# untitled.net
KiCad netlist of a schematic drawn in EAGLE
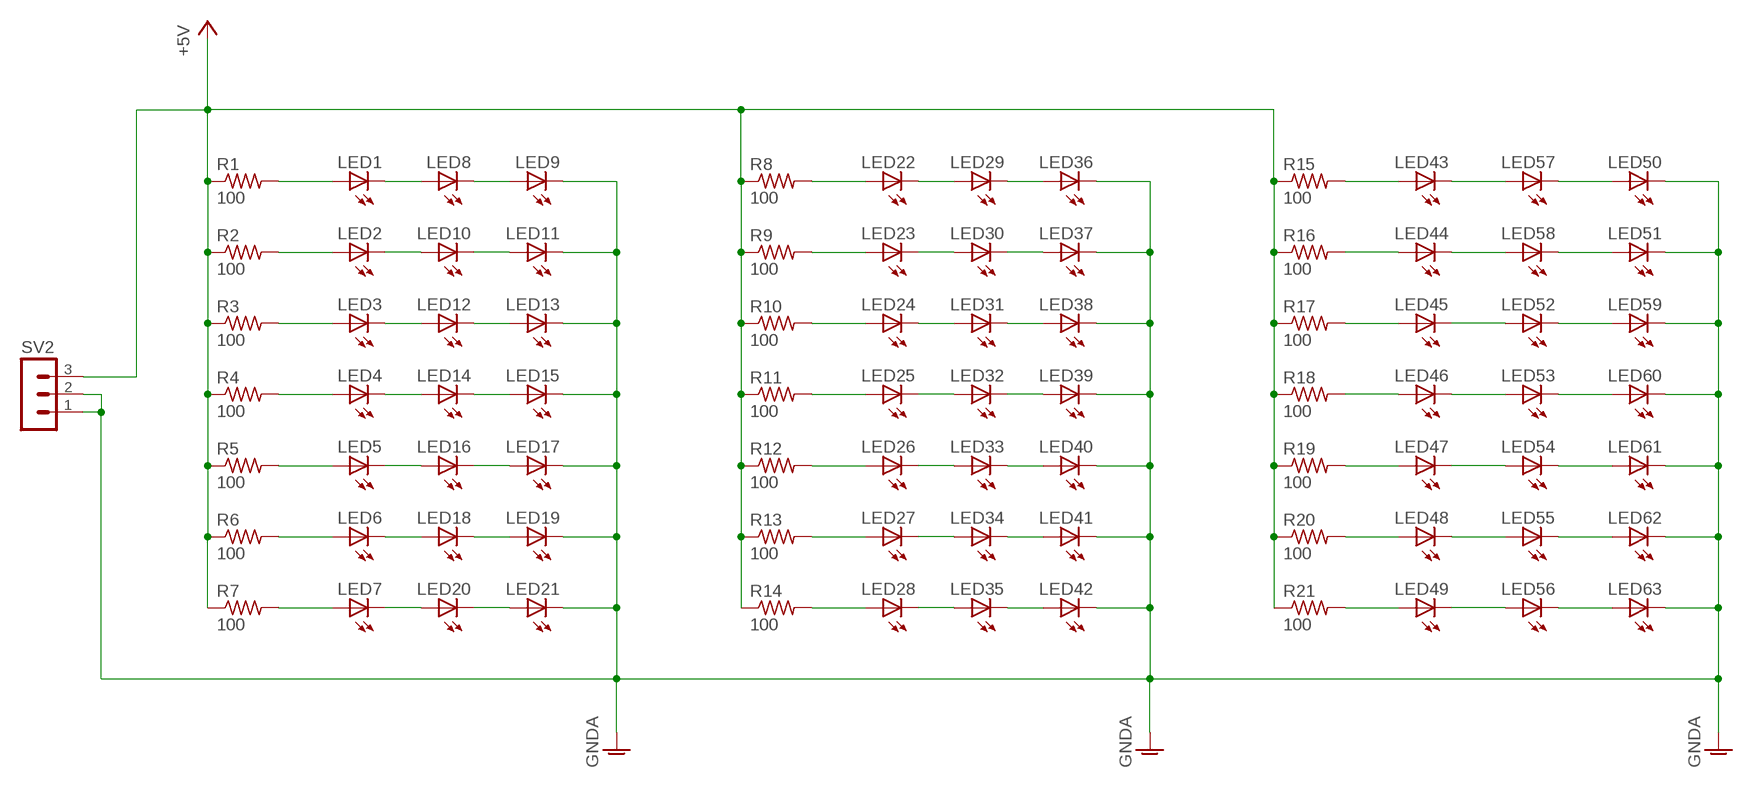
[diagram p0: schematic, sheet 1]

(export (version "E")
  (design (tool "Eeschema 10.0.6"))
  (components
    (comp (ref "LED1")
      (value "LED5MM")
      (footprint "eagle-import:LED5MM")
      (libsource (lib "eagle-import") (part "LED5MM"))
    )
    (comp (ref "LED2")
      (value "LED5MM")
      (footprint "eagle-import:LED5MM")
      (libsource (lib "eagle-import") (part "LED5MM"))
    )
    (comp (ref "LED3")
      (value "LED5MM")
      (footprint "eagle-import:LED5MM")
      (libsource (lib "eagle-import") (part "LED5MM"))
    )
    (comp (ref "LED4")
      (value "LED5MM")
      (footprint "eagle-import:LED5MM")
      (libsource (lib "eagle-import") (part "LED5MM"))
    )
    (comp (ref "LED5")
      (value "LED5MM")
      (footprint "eagle-import:LED5MM")
      (libsource (lib "eagle-import") (part "LED5MM"))
    )
    (comp (ref "LED6")
      (value "LED5MM")
      (footprint "eagle-import:LED5MM")
      (libsource (lib "eagle-import") (part "LED5MM"))
    )
    (comp (ref "LED7")
      (value "LED5MM")
      (footprint "eagle-import:LED5MM")
      (libsource (lib "eagle-import") (part "LED5MM"))
    )
    (comp (ref "LED8")
      (value "LED5MM")
      (footprint "eagle-import:LED5MM")
      (libsource (lib "eagle-import") (part "LED5MM"))
    )
    (comp (ref "LED9")
      (value "LED5MM")
      (footprint "eagle-import:LED5MM")
      (libsource (lib "eagle-import") (part "LED5MM"))
    )
    (comp (ref "LED10")
      (value "LED5MM")
      (footprint "eagle-import:LED5MM")
      (libsource (lib "eagle-import") (part "LED5MM"))
    )
    (comp (ref "LED11")
      (value "LED5MM")
      (footprint "eagle-import:LED5MM")
      (libsource (lib "eagle-import") (part "LED5MM"))
    )
    (comp (ref "LED12")
      (value "LED5MM")
      (footprint "eagle-import:LED5MM")
      (libsource (lib "eagle-import") (part "LED5MM"))
    )
    (comp (ref "LED13")
      (value "LED5MM")
      (footprint "eagle-import:LED5MM")
      (libsource (lib "eagle-import") (part "LED5MM"))
    )
    (comp (ref "LED14")
      (value "LED5MM")
      (footprint "eagle-import:LED5MM")
      (libsource (lib "eagle-import") (part "LED5MM"))
    )
    (comp (ref "LED15")
      (value "LED5MM")
      (footprint "eagle-import:LED5MM")
      (libsource (lib "eagle-import") (part "LED5MM"))
    )
    (comp (ref "LED16")
      (value "LED5MM")
      (footprint "eagle-import:LED5MM")
      (libsource (lib "eagle-import") (part "LED5MM"))
    )
    (comp (ref "LED17")
      (value "LED5MM")
      (footprint "eagle-import:LED5MM")
      (libsource (lib "eagle-import") (part "LED5MM"))
    )
    (comp (ref "LED18")
      (value "LED5MM")
      (footprint "eagle-import:LED5MM")
      (libsource (lib "eagle-import") (part "LED5MM"))
    )
    (comp (ref "LED19")
      (value "LED5MM")
      (footprint "eagle-import:LED5MM")
      (libsource (lib "eagle-import") (part "LED5MM"))
    )
    (comp (ref "LED20")
      (value "LED5MM")
      (footprint "eagle-import:LED5MM")
      (libsource (lib "eagle-import") (part "LED5MM"))
    )
    (comp (ref "LED21")
      (value "LED5MM")
      (footprint "eagle-import:LED5MM")
      (libsource (lib "eagle-import") (part "LED5MM"))
    )
    (comp (ref "LED22")
      (value "LED5MM")
      (footprint "eagle-import:LED5MM")
      (libsource (lib "eagle-import") (part "LED5MM"))
    )
    (comp (ref "LED23")
      (value "LED5MM")
      (footprint "eagle-import:LED5MM")
      (libsource (lib "eagle-import") (part "LED5MM"))
    )
    (comp (ref "LED24")
      (value "LED5MM")
      (footprint "eagle-import:LED5MM")
      (libsource (lib "eagle-import") (part "LED5MM"))
    )
    (comp (ref "LED25")
      (value "LED5MM")
      (footprint "eagle-import:LED5MM")
      (libsource (lib "eagle-import") (part "LED5MM"))
    )
    (comp (ref "LED26")
      (value "LED5MM")
      (footprint "eagle-import:LED5MM")
      (libsource (lib "eagle-import") (part "LED5MM"))
    )
    (comp (ref "LED27")
      (value "LED5MM")
      (footprint "eagle-import:LED5MM")
      (libsource (lib "eagle-import") (part "LED5MM"))
    )
    (comp (ref "LED28")
      (value "LED5MM")
      (footprint "eagle-import:LED5MM")
      (libsource (lib "eagle-import") (part "LED5MM"))
    )
    (comp (ref "LED29")
      (value "LED5MM")
      (footprint "eagle-import:LED5MM")
      (libsource (lib "eagle-import") (part "LED5MM"))
    )
    (comp (ref "LED30")
      (value "LED5MM")
      (footprint "eagle-import:LED5MM")
      (libsource (lib "eagle-import") (part "LED5MM"))
    )
    (comp (ref "LED31")
      (value "LED5MM")
      (footprint "eagle-import:LED5MM")
      (libsource (lib "eagle-import") (part "LED5MM"))
    )
    (comp (ref "LED32")
      (value "LED5MM")
      (footprint "eagle-import:LED5MM")
      (libsource (lib "eagle-import") (part "LED5MM"))
    )
    (comp (ref "LED33")
      (value "LED5MM")
      (footprint "eagle-import:LED5MM")
      (libsource (lib "eagle-import") (part "LED5MM"))
    )
    (comp (ref "LED34")
      (value "LED5MM")
      (footprint "eagle-import:LED5MM")
      (libsource (lib "eagle-import") (part "LED5MM"))
    )
    (comp (ref "LED35")
      (value "LED5MM")
      (footprint "eagle-import:LED5MM")
      (libsource (lib "eagle-import") (part "LED5MM"))
    )
    (comp (ref "LED36")
      (value "LED5MM")
      (footprint "eagle-import:LED5MM")
      (libsource (lib "eagle-import") (part "LED5MM"))
    )
    (comp (ref "LED37")
      (value "LED5MM")
      (footprint "eagle-import:LED5MM")
      (libsource (lib "eagle-import") (part "LED5MM"))
    )
    (comp (ref "LED38")
      (value "LED5MM")
      (footprint "eagle-import:LED5MM")
      (libsource (lib "eagle-import") (part "LED5MM"))
    )
    (comp (ref "LED39")
      (value "LED5MM")
      (footprint "eagle-import:LED5MM")
      (libsource (lib "eagle-import") (part "LED5MM"))
    )
    (comp (ref "LED40")
      (value "LED5MM")
      (footprint "eagle-import:LED5MM")
      (libsource (lib "eagle-import") (part "LED5MM"))
    )
    (comp (ref "LED41")
      (value "LED5MM")
      (footprint "eagle-import:LED5MM")
      (libsource (lib "eagle-import") (part "LED5MM"))
    )
    (comp (ref "LED42")
      (value "LED5MM")
      (footprint "eagle-import:LED5MM")
      (libsource (lib "eagle-import") (part "LED5MM"))
    )
    (comp (ref "LED43")
      (value "LED5MM")
      (footprint "eagle-import:LED5MM")
      (libsource (lib "eagle-import") (part "LED5MM"))
    )
    (comp (ref "LED44")
      (value "LED5MM")
      (footprint "eagle-import:LED5MM")
      (libsource (lib "eagle-import") (part "LED5MM"))
    )
    (comp (ref "LED45")
      (value "LED5MM")
      (footprint "eagle-import:LED5MM")
      (libsource (lib "eagle-import") (part "LED5MM"))
    )
    (comp (ref "LED46")
      (value "LED5MM")
      (footprint "eagle-import:LED5MM")
      (libsource (lib "eagle-import") (part "LED5MM"))
    )
    (comp (ref "LED47")
      (value "LED5MM")
      (footprint "eagle-import:LED5MM")
      (libsource (lib "eagle-import") (part "LED5MM"))
    )
    (comp (ref "LED48")
      (value "LED5MM")
      (footprint "eagle-import:LED5MM")
      (libsource (lib "eagle-import") (part "LED5MM"))
    )
    (comp (ref "LED49")
      (value "LED5MM")
      (footprint "eagle-import:LED5MM")
      (libsource (lib "eagle-import") (part "LED5MM"))
    )
    (comp (ref "LED50")
      (value "LED5MM")
      (footprint "eagle-import:LED5MM")
      (libsource (lib "eagle-import") (part "LED5MM"))
    )
    (comp (ref "LED51")
      (value "LED5MM")
      (footprint "eagle-import:LED5MM")
      (libsource (lib "eagle-import") (part "LED5MM"))
    )
    (comp (ref "LED52")
      (value "LED5MM")
      (footprint "eagle-import:LED5MM")
      (libsource (lib "eagle-import") (part "LED5MM"))
    )
    (comp (ref "LED53")
      (value "LED5MM")
      (footprint "eagle-import:LED5MM")
      (libsource (lib "eagle-import") (part "LED5MM"))
    )
    (comp (ref "LED54")
      (value "LED5MM")
      (footprint "eagle-import:LED5MM")
      (libsource (lib "eagle-import") (part "LED5MM"))
    )
    (comp (ref "LED55")
      (value "LED5MM")
      (footprint "eagle-import:LED5MM")
      (libsource (lib "eagle-import") (part "LED5MM"))
    )
    (comp (ref "LED56")
      (value "LED5MM")
      (footprint "eagle-import:LED5MM")
      (libsource (lib "eagle-import") (part "LED5MM"))
    )
    (comp (ref "LED57")
      (value "LED5MM")
      (footprint "eagle-import:LED5MM")
      (libsource (lib "eagle-import") (part "LED5MM"))
    )
    (comp (ref "LED58")
      (value "LED5MM")
      (footprint "eagle-import:LED5MM")
      (libsource (lib "eagle-import") (part "LED5MM"))
    )
    (comp (ref "LED59")
      (value "LED5MM")
      (footprint "eagle-import:LED5MM")
      (libsource (lib "eagle-import") (part "LED5MM"))
    )
    (comp (ref "LED60")
      (value "LED5MM")
      (footprint "eagle-import:LED5MM")
      (libsource (lib "eagle-import") (part "LED5MM"))
    )
    (comp (ref "LED61")
      (value "LED5MM")
      (footprint "eagle-import:LED5MM")
      (libsource (lib "eagle-import") (part "LED5MM"))
    )
    (comp (ref "LED62")
      (value "LED5MM")
      (footprint "eagle-import:LED5MM")
      (libsource (lib "eagle-import") (part "LED5MM"))
    )
    (comp (ref "LED63")
      (value "LED5MM")
      (footprint "eagle-import:LED5MM")
      (libsource (lib "eagle-import") (part "LED5MM"))
    )
    (comp (ref "R1")
      (value "100")
      (footprint "eagle-import:0204_5")
      (libsource (lib "eagle-import") (part "R-US_0204/5"))
    )
    (comp (ref "R2")
      (value "100")
      (footprint "eagle-import:0204_5")
      (libsource (lib "eagle-import") (part "R-US_0204/5"))
    )
    (comp (ref "R3")
      (value "100")
      (footprint "eagle-import:0204_5")
      (libsource (lib "eagle-import") (part "R-US_0204/5"))
    )
    (comp (ref "R4")
      (value "100")
      (footprint "eagle-import:0204_5")
      (libsource (lib "eagle-import") (part "R-US_0204/5"))
    )
    (comp (ref "R5")
      (value "100")
      (footprint "eagle-import:0204_5")
      (libsource (lib "eagle-import") (part "R-US_0204/5"))
    )
    (comp (ref "R6")
      (value "100")
      (footprint "eagle-import:0204_5")
      (libsource (lib "eagle-import") (part "R-US_0204/5"))
    )
    (comp (ref "R7")
      (value "100")
      (footprint "eagle-import:0204_5")
      (libsource (lib "eagle-import") (part "R-US_0204/5"))
    )
    (comp (ref "R8")
      (value "100")
      (footprint "eagle-import:0204_5")
      (libsource (lib "eagle-import") (part "R-US_0204/5"))
    )
    (comp (ref "R9")
      (value "100")
      (footprint "eagle-import:0204_5")
      (libsource (lib "eagle-import") (part "R-US_0204/5"))
    )
    (comp (ref "R10")
      (value "100")
      (footprint "eagle-import:0204_5")
      (libsource (lib "eagle-import") (part "R-US_0204/5"))
    )
    (comp (ref "R11")
      (value "100")
      (footprint "eagle-import:0204_5")
      (libsource (lib "eagle-import") (part "R-US_0204/5"))
    )
    (comp (ref "R12")
      (value "100")
      (footprint "eagle-import:0204_5")
      (libsource (lib "eagle-import") (part "R-US_0204/5"))
    )
    (comp (ref "R13")
      (value "100")
      (footprint "eagle-import:0204_5")
      (libsource (lib "eagle-import") (part "R-US_0204/5"))
    )
    (comp (ref "R14")
      (value "100")
      (footprint "eagle-import:0204_5")
      (libsource (lib "eagle-import") (part "R-US_0204/5"))
    )
    (comp (ref "R15")
      (value "100")
      (footprint "eagle-import:0204_5")
      (libsource (lib "eagle-import") (part "R-US_0204/5"))
    )
    (comp (ref "R16")
      (value "100")
      (footprint "eagle-import:0204_5")
      (libsource (lib "eagle-import") (part "R-US_0204/5"))
    )
    (comp (ref "R17")
      (value "100")
      (footprint "eagle-import:0204_5")
      (libsource (lib "eagle-import") (part "R-US_0204/5"))
    )
    (comp (ref "R18")
      (value "100")
      (footprint "eagle-import:0204_5")
      (libsource (lib "eagle-import") (part "R-US_0204/5"))
    )
    (comp (ref "R19")
      (value "100")
      (footprint "eagle-import:0204_5")
      (libsource (lib "eagle-import") (part "R-US_0204/5"))
    )
    (comp (ref "R20")
      (value "100")
      (footprint "eagle-import:0204_5")
      (libsource (lib "eagle-import") (part "R-US_0204/5"))
    )
    (comp (ref "R21")
      (value "100")
      (footprint "eagle-import:0204_5")
      (libsource (lib "eagle-import") (part "R-US_0204/5"))
    )
    (comp (ref "SV2")
      (value "MA03-1")
      (footprint "eagle-import:MA03-1")
      (libsource (lib "eagle-import") (part "MA03-1"))
    )
  )
  (nets
    (net (code "1") (name "+5V") (class "Default")
      (node (ref "R1") (pin "1") (pinfunction "1_1") (pintype "passive"))
      (node (ref "R10") (pin "1") (pinfunction "1_1") (pintype "passive"))
      (node (ref "R11") (pin "1") (pinfunction "1_1") (pintype "passive"))
      (node (ref "R12") (pin "1") (pinfunction "1_1") (pintype "passive"))
      (node (ref "R13") (pin "1") (pinfunction "1_1") (pintype "passive"))
      (node (ref "R14") (pin "1") (pinfunction "1_1") (pintype "passive"))
      (node (ref "R15") (pin "1") (pinfunction "1_1") (pintype "passive"))
      (node (ref "R16") (pin "1") (pinfunction "1_1") (pintype "passive"))
      (node (ref "R17") (pin "1") (pinfunction "1_1") (pintype "passive"))
      (node (ref "R18") (pin "1") (pinfunction "1_1") (pintype "passive"))
      (node (ref "R19") (pin "1") (pinfunction "1_1") (pintype "passive"))
      (node (ref "R2") (pin "1") (pinfunction "1_1") (pintype "passive"))
      (node (ref "R20") (pin "1") (pinfunction "1_1") (pintype "passive"))
      (node (ref "R21") (pin "1") (pinfunction "1_1") (pintype "passive"))
      (node (ref "R3") (pin "1") (pinfunction "1_1") (pintype "passive"))
      (node (ref "R4") (pin "1") (pinfunction "1_1") (pintype "passive"))
      (node (ref "R5") (pin "1") (pinfunction "1_1") (pintype "passive"))
      (node (ref "R6") (pin "1") (pinfunction "1_1") (pintype "passive"))
      (node (ref "R7") (pin "1") (pinfunction "1_1") (pintype "passive"))
      (node (ref "R8") (pin "1") (pinfunction "1_1") (pintype "passive"))
      (node (ref "R9") (pin "1") (pinfunction "1_1") (pintype "passive"))
      (node (ref "SV2") (pin "3") (pinfunction "3_3") (pintype "passive"))
    )
    (net (code "2") (name "GNDA") (class "Default")
      (node (ref "LED11") (pin "K") (pinfunction "C_K") (pintype "passive"))
      (node (ref "LED13") (pin "K") (pinfunction "C_K") (pintype "passive"))
      (node (ref "LED15") (pin "K") (pinfunction "C_K") (pintype "passive"))
      (node (ref "LED17") (pin "K") (pinfunction "C_K") (pintype "passive"))
      (node (ref "LED19") (pin "K") (pinfunction "C_K") (pintype "passive"))
      (node (ref "LED21") (pin "K") (pinfunction "C_K") (pintype "passive"))
      (node (ref "LED36") (pin "K") (pinfunction "C_K") (pintype "passive"))
      (node (ref "LED37") (pin "K") (pinfunction "C_K") (pintype "passive"))
      (node (ref "LED38") (pin "K") (pinfunction "C_K") (pintype "passive"))
      (node (ref "LED39") (pin "K") (pinfunction "C_K") (pintype "passive"))
      (node (ref "LED40") (pin "K") (pinfunction "C_K") (pintype "passive"))
      (node (ref "LED41") (pin "K") (pinfunction "C_K") (pintype "passive"))
      (node (ref "LED42") (pin "K") (pinfunction "C_K") (pintype "passive"))
      (node (ref "LED50") (pin "K") (pinfunction "C_K") (pintype "passive"))
      (node (ref "LED51") (pin "K") (pinfunction "C_K") (pintype "passive"))
      (node (ref "LED59") (pin "K") (pinfunction "C_K") (pintype "passive"))
      (node (ref "LED60") (pin "K") (pinfunction "C_K") (pintype "passive"))
      (node (ref "LED61") (pin "K") (pinfunction "C_K") (pintype "passive"))
      (node (ref "LED62") (pin "K") (pinfunction "C_K") (pintype "passive"))
      (node (ref "LED63") (pin "K") (pinfunction "C_K") (pintype "passive"))
      (node (ref "LED9") (pin "K") (pinfunction "C_K") (pintype "passive"))
      (node (ref "SV2") (pin "1") (pinfunction "1_1") (pintype "passive"))
      (node (ref "SV2") (pin "2") (pinfunction "2_2") (pintype "passive"))
    )
    (net (code "3") (name "Net-(LED1-C)") (class "Default")
      (node (ref "LED1") (pin "K") (pinfunction "C_K") (pintype "passive"))
      (node (ref "LED8") (pin "A") (pinfunction "A_A") (pintype "passive"))
    )
    (net (code "4") (name "Net-(LED1-PadA)") (class "Default")
      (node (ref "LED1") (pin "A") (pinfunction "A_A") (pintype "passive"))
      (node (ref "R1") (pin "2") (pinfunction "2_2") (pintype "passive"))
    )
    (net (code "5") (name "Net-(LED2-C)") (class "Default")
      (node (ref "LED10") (pin "A") (pinfunction "A_A") (pintype "passive"))
      (node (ref "LED2") (pin "K") (pinfunction "C_K") (pintype "passive"))
    )
    (net (code "6") (name "Net-(LED2-PadA)") (class "Default")
      (node (ref "LED2") (pin "A") (pinfunction "A_A") (pintype "passive"))
      (node (ref "R2") (pin "2") (pinfunction "2_2") (pintype "passive"))
    )
    (net (code "7") (name "Net-(LED3-C)") (class "Default")
      (node (ref "LED12") (pin "A") (pinfunction "A_A") (pintype "passive"))
      (node (ref "LED3") (pin "K") (pinfunction "C_K") (pintype "passive"))
    )
    (net (code "8") (name "Net-(LED3-PadA)") (class "Default")
      (node (ref "LED3") (pin "A") (pinfunction "A_A") (pintype "passive"))
      (node (ref "R3") (pin "2") (pinfunction "2_2") (pintype "passive"))
    )
    (net (code "9") (name "Net-(LED4-C)") (class "Default")
      (node (ref "LED14") (pin "A") (pinfunction "A_A") (pintype "passive"))
      (node (ref "LED4") (pin "K") (pinfunction "C_K") (pintype "passive"))
    )
    (net (code "10") (name "Net-(LED4-PadA)") (class "Default")
      (node (ref "LED4") (pin "A") (pinfunction "A_A") (pintype "passive"))
      (node (ref "R4") (pin "2") (pinfunction "2_2") (pintype "passive"))
    )
    (net (code "11") (name "Net-(LED5-C)") (class "Default")
      (node (ref "LED16") (pin "A") (pinfunction "A_A") (pintype "passive"))
      (node (ref "LED5") (pin "K") (pinfunction "C_K") (pintype "passive"))
    )
    (net (code "12") (name "Net-(LED5-PadA)") (class "Default")
      (node (ref "LED5") (pin "A") (pinfunction "A_A") (pintype "passive"))
      (node (ref "R5") (pin "2") (pinfunction "2_2") (pintype "passive"))
    )
    (net (code "13") (name "Net-(LED6-C)") (class "Default")
      (node (ref "LED18") (pin "A") (pinfunction "A_A") (pintype "passive"))
      (node (ref "LED6") (pin "K") (pinfunction "C_K") (pintype "passive"))
    )
    (net (code "14") (name "Net-(LED6-PadA)") (class "Default")
      (node (ref "LED6") (pin "A") (pinfunction "A_A") (pintype "passive"))
      (node (ref "R6") (pin "2") (pinfunction "2_2") (pintype "passive"))
    )
    (net (code "15") (name "Net-(LED7-C)") (class "Default")
      (node (ref "LED20") (pin "A") (pinfunction "A_A") (pintype "passive"))
      (node (ref "LED7") (pin "K") (pinfunction "C_K") (pintype "passive"))
    )
    (net (code "16") (name "Net-(LED7-PadA)") (class "Default")
      (node (ref "LED7") (pin "A") (pinfunction "A_A") (pintype "passive"))
      (node (ref "R7") (pin "2") (pinfunction "2_2") (pintype "passive"))
    )
    (net (code "17") (name "Net-(LED8-C)") (class "Default")
      (node (ref "LED8") (pin "K") (pinfunction "C_K") (pintype "passive"))
      (node (ref "LED9") (pin "A") (pinfunction "A_A") (pintype "passive"))
    )
    (net (code "18") (name "Net-(LED10-C)") (class "Default")
      (node (ref "LED10") (pin "K") (pinfunction "C_K") (pintype "passive"))
      (node (ref "LED11") (pin "A") (pinfunction "A_A") (pintype "passive"))
    )
    (net (code "19") (name "Net-(LED12-C)") (class "Default")
      (node (ref "LED12") (pin "K") (pinfunction "C_K") (pintype "passive"))
      (node (ref "LED13") (pin "A") (pinfunction "A_A") (pintype "passive"))
    )
    (net (code "20") (name "Net-(LED14-C)") (class "Default")
      (node (ref "LED14") (pin "K") (pinfunction "C_K") (pintype "passive"))
      (node (ref "LED15") (pin "A") (pinfunction "A_A") (pintype "passive"))
    )
    (net (code "21") (name "Net-(LED16-C)") (class "Default")
      (node (ref "LED16") (pin "K") (pinfunction "C_K") (pintype "passive"))
      (node (ref "LED17") (pin "A") (pinfunction "A_A") (pintype "passive"))
    )
    (net (code "22") (name "Net-(LED18-C)") (class "Default")
      (node (ref "LED18") (pin "K") (pinfunction "C_K") (pintype "passive"))
      (node (ref "LED19") (pin "A") (pinfunction "A_A") (pintype "passive"))
    )
    (net (code "23") (name "Net-(LED20-C)") (class "Default")
      (node (ref "LED20") (pin "K") (pinfunction "C_K") (pintype "passive"))
      (node (ref "LED21") (pin "A") (pinfunction "A_A") (pintype "passive"))
    )
    (net (code "24") (name "Net-(LED22-C)") (class "Default")
      (node (ref "LED22") (pin "K") (pinfunction "C_K") (pintype "passive"))
      (node (ref "LED29") (pin "A") (pinfunction "A_A") (pintype "passive"))
    )
    (net (code "25") (name "Net-(LED22-PadA)") (class "Default")
      (node (ref "LED22") (pin "A") (pinfunction "A_A") (pintype "passive"))
      (node (ref "R8") (pin "2") (pinfunction "2_2") (pintype "passive"))
    )
    (net (code "26") (name "Net-(LED23-C)") (class "Default")
      (node (ref "LED23") (pin "K") (pinfunction "C_K") (pintype "passive"))
      (node (ref "LED30") (pin "A") (pinfunction "A_A") (pintype "passive"))
    )
    (net (code "27") (name "Net-(LED23-PadA)") (class "Default")
      (node (ref "LED23") (pin "A") (pinfunction "A_A") (pintype "passive"))
      (node (ref "R9") (pin "2") (pinfunction "2_2") (pintype "passive"))
    )
    (net (code "28") (name "Net-(LED24-C)") (class "Default")
      (node (ref "LED24") (pin "K") (pinfunction "C_K") (pintype "passive"))
      (node (ref "LED31") (pin "A") (pinfunction "A_A") (pintype "passive"))
    )
    (net (code "29") (name "Net-(LED24-PadA)") (class "Default")
      (node (ref "LED24") (pin "A") (pinfunction "A_A") (pintype "passive"))
      (node (ref "R10") (pin "2") (pinfunction "2_2") (pintype "passive"))
    )
    (net (code "30") (name "Net-(LED25-C)") (class "Default")
      (node (ref "LED25") (pin "K") (pinfunction "C_K") (pintype "passive"))
      (node (ref "LED32") (pin "A") (pinfunction "A_A") (pintype "passive"))
    )
    (net (code "31") (name "Net-(LED25-PadA)") (class "Default")
      (node (ref "LED25") (pin "A") (pinfunction "A_A") (pintype "passive"))
      (node (ref "R11") (pin "2") (pinfunction "2_2") (pintype "passive"))
    )
    (net (code "32") (name "Net-(LED26-C)") (class "Default")
      (node (ref "LED26") (pin "K") (pinfunction "C_K") (pintype "passive"))
      (node (ref "LED33") (pin "A") (pinfunction "A_A") (pintype "passive"))
    )
    (net (code "33") (name "Net-(LED26-PadA)") (class "Default")
      (node (ref "LED26") (pin "A") (pinfunction "A_A") (pintype "passive"))
      (node (ref "R12") (pin "2") (pinfunction "2_2") (pintype "passive"))
    )
    (net (code "34") (name "Net-(LED27-C)") (class "Default")
      (node (ref "LED27") (pin "K") (pinfunction "C_K") (pintype "passive"))
      (node (ref "LED34") (pin "A") (pinfunction "A_A") (pintype "passive"))
    )
    (net (code "35") (name "Net-(LED27-PadA)") (class "Default")
      (node (ref "LED27") (pin "A") (pinfunction "A_A") (pintype "passive"))
      (node (ref "R13") (pin "2") (pinfunction "2_2") (pintype "passive"))
    )
    (net (code "36") (name "Net-(LED28-C)") (class "Default")
      (node (ref "LED28") (pin "K") (pinfunction "C_K") (pintype "passive"))
      (node (ref "LED35") (pin "A") (pinfunction "A_A") (pintype "passive"))
    )
    (net (code "37") (name "Net-(LED28-PadA)") (class "Default")
      (node (ref "LED28") (pin "A") (pinfunction "A_A") (pintype "passive"))
      (node (ref "R14") (pin "2") (pinfunction "2_2") (pintype "passive"))
    )
    (net (code "38") (name "Net-(LED29-C)") (class "Default")
      (node (ref "LED29") (pin "K") (pinfunction "C_K") (pintype "passive"))
      (node (ref "LED36") (pin "A") (pinfunction "A_A") (pintype "passive"))
    )
    (net (code "39") (name "Net-(LED30-C)") (class "Default")
      (node (ref "LED30") (pin "K") (pinfunction "C_K") (pintype "passive"))
      (node (ref "LED37") (pin "A") (pinfunction "A_A") (pintype "passive"))
    )
    (net (code "40") (name "Net-(LED31-C)") (class "Default")
      (node (ref "LED31") (pin "K") (pinfunction "C_K") (pintype "passive"))
      (node (ref "LED38") (pin "A") (pinfunction "A_A") (pintype "passive"))
    )
    (net (code "41") (name "Net-(LED32-C)") (class "Default")
      (node (ref "LED32") (pin "K") (pinfunction "C_K") (pintype "passive"))
      (node (ref "LED39") (pin "A") (pinfunction "A_A") (pintype "passive"))
    )
    (net (code "42") (name "Net-(LED33-C)") (class "Default")
      (node (ref "LED33") (pin "K") (pinfunction "C_K") (pintype "passive"))
      (node (ref "LED40") (pin "A") (pinfunction "A_A") (pintype "passive"))
    )
    (net (code "43") (name "Net-(LED34-C)") (class "Default")
      (node (ref "LED34") (pin "K") (pinfunction "C_K") (pintype "passive"))
      (node (ref "LED41") (pin "A") (pinfunction "A_A") (pintype "passive"))
    )
    (net (code "44") (name "Net-(LED35-C)") (class "Default")
      (node (ref "LED35") (pin "K") (pinfunction "C_K") (pintype "passive"))
      (node (ref "LED42") (pin "A") (pinfunction "A_A") (pintype "passive"))
    )
    (net (code "45") (name "Net-(LED43-C)") (class "Default")
      (node (ref "LED43") (pin "K") (pinfunction "C_K") (pintype "passive"))
      (node (ref "LED57") (pin "A") (pinfunction "A_A") (pintype "passive"))
    )
    (net (code "46") (name "Net-(LED43-PadA)") (class "Default")
      (node (ref "LED43") (pin "A") (pinfunction "A_A") (pintype "passive"))
      (node (ref "R15") (pin "2") (pinfunction "2_2") (pintype "passive"))
    )
    (net (code "47") (name "Net-(LED44-C)") (class "Default")
      (node (ref "LED44") (pin "K") (pinfunction "C_K") (pintype "passive"))
      (node (ref "LED58") (pin "A") (pinfunction "A_A") (pintype "passive"))
    )
    (net (code "48") (name "Net-(LED44-PadA)") (class "Default")
      (node (ref "LED44") (pin "A") (pinfunction "A_A") (pintype "passive"))
      (node (ref "R16") (pin "2") (pinfunction "2_2") (pintype "passive"))
    )
    (net (code "49") (name "Net-(LED45-C)") (class "Default")
      (node (ref "LED45") (pin "K") (pinfunction "C_K") (pintype "passive"))
      (node (ref "LED52") (pin "A") (pinfunction "A_A") (pintype "passive"))
    )
    (net (code "50") (name "Net-(LED45-PadA)") (class "Default")
      (node (ref "LED45") (pin "A") (pinfunction "A_A") (pintype "passive"))
      (node (ref "R17") (pin "2") (pinfunction "2_2") (pintype "passive"))
    )
    (net (code "51") (name "Net-(LED46-C)") (class "Default")
      (node (ref "LED46") (pin "K") (pinfunction "C_K") (pintype "passive"))
      (node (ref "LED53") (pin "A") (pinfunction "A_A") (pintype "passive"))
    )
    (net (code "52") (name "Net-(LED46-PadA)") (class "Default")
      (node (ref "LED46") (pin "A") (pinfunction "A_A") (pintype "passive"))
      (node (ref "R18") (pin "2") (pinfunction "2_2") (pintype "passive"))
    )
    (net (code "53") (name "Net-(LED47-C)") (class "Default")
      (node (ref "LED47") (pin "K") (pinfunction "C_K") (pintype "passive"))
      (node (ref "LED54") (pin "A") (pinfunction "A_A") (pintype "passive"))
    )
    (net (code "54") (name "Net-(LED47-PadA)") (class "Default")
      (node (ref "LED47") (pin "A") (pinfunction "A_A") (pintype "passive"))
      (node (ref "R19") (pin "2") (pinfunction "2_2") (pintype "passive"))
    )
    (net (code "55") (name "Net-(LED48-C)") (class "Default")
      (node (ref "LED48") (pin "K") (pinfunction "C_K") (pintype "passive"))
      (node (ref "LED55") (pin "A") (pinfunction "A_A") (pintype "passive"))
    )
    (net (code "56") (name "Net-(LED48-PadA)") (class "Default")
      (node (ref "LED48") (pin "A") (pinfunction "A_A") (pintype "passive"))
      (node (ref "R20") (pin "2") (pinfunction "2_2") (pintype "passive"))
    )
    (net (code "57") (name "Net-(LED49-C)") (class "Default")
      (node (ref "LED49") (pin "K") (pinfunction "C_K") (pintype "passive"))
      (node (ref "LED56") (pin "A") (pinfunction "A_A") (pintype "passive"))
    )
    (net (code "58") (name "Net-(LED49-PadA)") (class "Default")
      (node (ref "LED49") (pin "A") (pinfunction "A_A") (pintype "passive"))
      (node (ref "R21") (pin "2") (pinfunction "2_2") (pintype "passive"))
    )
    (net (code "59") (name "Net-(LED52-C)") (class "Default")
      (node (ref "LED52") (pin "K") (pinfunction "C_K") (pintype "passive"))
      (node (ref "LED59") (pin "A") (pinfunction "A_A") (pintype "passive"))
    )
    (net (code "60") (name "Net-(LED53-C)") (class "Default")
      (node (ref "LED53") (pin "K") (pinfunction "C_K") (pintype "passive"))
      (node (ref "LED60") (pin "A") (pinfunction "A_A") (pintype "passive"))
    )
    (net (code "61") (name "Net-(LED54-C)") (class "Default")
      (node (ref "LED54") (pin "K") (pinfunction "C_K") (pintype "passive"))
      (node (ref "LED61") (pin "A") (pinfunction "A_A") (pintype "passive"))
    )
    (net (code "62") (name "Net-(LED55-C)") (class "Default")
      (node (ref "LED55") (pin "K") (pinfunction "C_K") (pintype "passive"))
      (node (ref "LED62") (pin "A") (pinfunction "A_A") (pintype "passive"))
    )
    (net (code "63") (name "Net-(LED56-C)") (class "Default")
      (node (ref "LED56") (pin "K") (pinfunction "C_K") (pintype "passive"))
      (node (ref "LED63") (pin "A") (pinfunction "A_A") (pintype "passive"))
    )
    (net (code "64") (name "Net-(LED57-C)") (class "Default")
      (node (ref "LED50") (pin "A") (pinfunction "A_A") (pintype "passive"))
      (node (ref "LED57") (pin "K") (pinfunction "C_K") (pintype "passive"))
    )
    (net (code "65") (name "Net-(LED58-C)") (class "Default")
      (node (ref "LED51") (pin "A") (pinfunction "A_A") (pintype "passive"))
      (node (ref "LED58") (pin "K") (pinfunction "C_K") (pintype "passive"))
    )
  )
)
